# E22-XXXMXXS.net
KiCad netlist of a schematic drawn in EAGLE
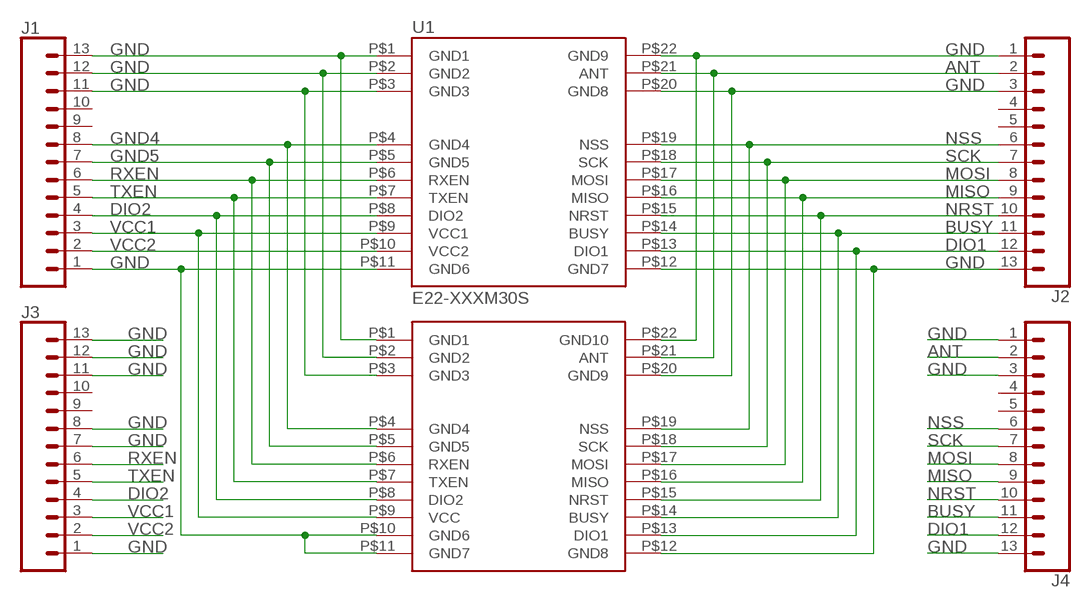
[diagram p0: schematic, sheet 1]

(export (version "E")
  (design (tool "Eeschema 10.0.6"))
  (components
    (comp (ref "J1")
      (value "CONN_13")
      (footprint "eagle-import:1X13")
      (libsource (lib "eagle-import") (part "CONN_13"))
    )
    (comp (ref "J2")
      (value "CONN_13")
      (footprint "eagle-import:1X13")
      (libsource (lib "eagle-import") (part "CONN_13"))
    )
    (comp (ref "J3")
      (value "CONN_13")
      (footprint "eagle-import:1X13")
      (libsource (lib "eagle-import") (part "CONN_13"))
    )
    (comp (ref "J4")
      (value "CONN_13")
      (footprint "eagle-import:1X13")
      (libsource (lib "eagle-import") (part "CONN_13"))
    )
    (comp (ref "U$1")
      (value "E22-XXXM22S")
      (footprint "eagle-import:E22-XXXM22S")
      (libsource (lib "eagle-import") (part "E22-XXXM22S"))
    )
    (comp (ref "U1")
      (value "E22-XXXM30S")
      (footprint "eagle-import:E22-XXXM30S")
      (libsource (lib "eagle-import") (part "E22-XXXM30S"))
    )
  )
  (nets
    (net (code "1") (name "/ANT") (class "Default")
      (node (ref "J2") (pin "2") (pinfunction "2_2") (pintype "passive"))
      (node (ref "J4") (pin "2") (pinfunction "2_2") (pintype "passive"))
      (node (ref "U$1") (pin "P$21") (pinfunction "ANT_P$21") (pintype "bidirectional"))
      (node (ref "U1") (pin "P$21") (pinfunction "ANT_P$21") (pintype "bidirectional"))
    )
    (net (code "2") (name "/BUSY") (class "Default")
      (node (ref "J2") (pin "11") (pinfunction "11_11") (pintype "passive"))
      (node (ref "J4") (pin "11") (pinfunction "11_11") (pintype "passive"))
      (node (ref "U$1") (pin "P$14") (pinfunction "BUSY_P$14") (pintype "bidirectional"))
      (node (ref "U1") (pin "P$14") (pinfunction "BUSY_P$14") (pintype "bidirectional"))
    )
    (net (code "3") (name "/DIO1") (class "Default")
      (node (ref "J2") (pin "12") (pinfunction "12_12") (pintype "passive"))
      (node (ref "J4") (pin "12") (pinfunction "12_12") (pintype "passive"))
      (node (ref "U$1") (pin "P$13") (pinfunction "DIO1_P$13") (pintype "bidirectional"))
      (node (ref "U1") (pin "P$13") (pinfunction "DIO1_P$13") (pintype "bidirectional"))
    )
    (net (code "4") (name "/DIO2") (class "Default")
      (node (ref "J1") (pin "4") (pinfunction "4_4") (pintype "passive"))
      (node (ref "J3") (pin "4") (pinfunction "4_4") (pintype "passive"))
      (node (ref "U$1") (pin "P$8") (pinfunction "DIO2_P$8") (pintype "bidirectional"))
      (node (ref "U1") (pin "P$8") (pinfunction "DIO2_P$8") (pintype "bidirectional"))
    )
    (net (code "5") (name "/GND") (class "Default")
      (node (ref "J1") (pin "1") (pinfunction "1_1") (pintype "passive"))
      (node (ref "J1") (pin "11") (pinfunction "11_11") (pintype "passive"))
      (node (ref "J1") (pin "12") (pinfunction "12_12") (pintype "passive"))
      (node (ref "J1") (pin "13") (pinfunction "13_13") (pintype "passive"))
      (node (ref "J2") (pin "1") (pinfunction "1_1") (pintype "passive"))
      (node (ref "J2") (pin "13") (pinfunction "13_13") (pintype "passive"))
      (node (ref "J2") (pin "3") (pinfunction "3_3") (pintype "passive"))
      (node (ref "J3") (pin "1") (pinfunction "1_1") (pintype "passive"))
      (node (ref "J3") (pin "11") (pinfunction "11_11") (pintype "passive"))
      (node (ref "J3") (pin "12") (pinfunction "12_12") (pintype "passive"))
      (node (ref "J3") (pin "13") (pinfunction "13_13") (pintype "passive"))
      (node (ref "J3") (pin "7") (pinfunction "7_7") (pintype "passive"))
      (node (ref "J3") (pin "8") (pinfunction "8_8") (pintype "passive"))
      (node (ref "J4") (pin "1") (pinfunction "1_1") (pintype "passive"))
      (node (ref "J4") (pin "13") (pinfunction "13_13") (pintype "passive"))
      (node (ref "J4") (pin "3") (pinfunction "3_3") (pintype "passive"))
      (node (ref "U$1") (pin "P$1") (pinfunction "GND1_P$1") (pintype "bidirectional"))
      (node (ref "U$1") (pin "P$10") (pinfunction "GND6_P$10") (pintype "bidirectional"))
      (node (ref "U$1") (pin "P$11") (pinfunction "GND7_P$11") (pintype "bidirectional"))
      (node (ref "U$1") (pin "P$12") (pinfunction "GND8_P$12") (pintype "bidirectional"))
      (node (ref "U$1") (pin "P$2") (pinfunction "GND2_P$2") (pintype "bidirectional"))
      (node (ref "U$1") (pin "P$20") (pinfunction "GND9_P$20") (pintype "bidirectional"))
      (node (ref "U$1") (pin "P$22") (pinfunction "GND10_P$22") (pintype "bidirectional"))
      (node (ref "U$1") (pin "P$3") (pinfunction "GND3_P$3") (pintype "bidirectional"))
      (node (ref "U1") (pin "P$1") (pinfunction "GND1_P$1") (pintype "bidirectional"))
      (node (ref "U1") (pin "P$11") (pinfunction "GND6_P$11") (pintype "bidirectional"))
      (node (ref "U1") (pin "P$12") (pinfunction "GND7_P$12") (pintype "bidirectional"))
      (node (ref "U1") (pin "P$2") (pinfunction "GND2_P$2") (pintype "bidirectional"))
      (node (ref "U1") (pin "P$20") (pinfunction "GND8_P$20") (pintype "bidirectional"))
      (node (ref "U1") (pin "P$22") (pinfunction "GND9_P$22") (pintype "bidirectional"))
      (node (ref "U1") (pin "P$3") (pinfunction "GND3_P$3") (pintype "bidirectional"))
    )
    (net (code "6") (name "/GND4") (class "Default")
      (node (ref "J1") (pin "8") (pinfunction "8_8") (pintype "passive"))
      (node (ref "U$1") (pin "P$4") (pinfunction "GND4_P$4") (pintype "bidirectional"))
      (node (ref "U1") (pin "P$4") (pinfunction "GND4_P$4") (pintype "bidirectional"))
    )
    (net (code "7") (name "/GND5") (class "Default")
      (node (ref "J1") (pin "7") (pinfunction "7_7") (pintype "passive"))
      (node (ref "U$1") (pin "P$5") (pinfunction "GND5_P$5") (pintype "bidirectional"))
      (node (ref "U1") (pin "P$5") (pinfunction "GND5_P$5") (pintype "bidirectional"))
    )
    (net (code "8") (name "/MISO") (class "Default")
      (node (ref "J2") (pin "9") (pinfunction "9_9") (pintype "passive"))
      (node (ref "J4") (pin "9") (pinfunction "9_9") (pintype "passive"))
      (node (ref "U$1") (pin "P$16") (pinfunction "MISO_P$16") (pintype "bidirectional"))
      (node (ref "U1") (pin "P$16") (pinfunction "MISO_P$16") (pintype "bidirectional"))
    )
    (net (code "9") (name "/MOSI") (class "Default")
      (node (ref "J2") (pin "8") (pinfunction "8_8") (pintype "passive"))
      (node (ref "J4") (pin "8") (pinfunction "8_8") (pintype "passive"))
      (node (ref "U$1") (pin "P$17") (pinfunction "MOSI_P$17") (pintype "bidirectional"))
      (node (ref "U1") (pin "P$17") (pinfunction "MOSI_P$17") (pintype "bidirectional"))
    )
    (net (code "10") (name "/NRST") (class "Default")
      (node (ref "J2") (pin "10") (pinfunction "10_10") (pintype "passive"))
      (node (ref "J4") (pin "10") (pinfunction "10_10") (pintype "passive"))
      (node (ref "U$1") (pin "P$15") (pinfunction "NRST_P$15") (pintype "bidirectional"))
      (node (ref "U1") (pin "P$15") (pinfunction "NRST_P$15") (pintype "bidirectional"))
    )
    (net (code "11") (name "/NSS") (class "Default")
      (node (ref "J2") (pin "6") (pinfunction "6_6") (pintype "passive"))
      (node (ref "J4") (pin "6") (pinfunction "6_6") (pintype "passive"))
      (node (ref "U$1") (pin "P$19") (pinfunction "NSS_P$19") (pintype "bidirectional"))
      (node (ref "U1") (pin "P$19") (pinfunction "NSS_P$19") (pintype "bidirectional"))
    )
    (net (code "12") (name "/RXEN") (class "Default")
      (node (ref "J1") (pin "6") (pinfunction "6_6") (pintype "passive"))
      (node (ref "J3") (pin "6") (pinfunction "6_6") (pintype "passive"))
      (node (ref "U$1") (pin "P$6") (pinfunction "RXEN_P$6") (pintype "bidirectional"))
      (node (ref "U1") (pin "P$6") (pinfunction "RXEN_P$6") (pintype "bidirectional"))
    )
    (net (code "13") (name "/SCK") (class "Default")
      (node (ref "J2") (pin "7") (pinfunction "7_7") (pintype "passive"))
      (node (ref "J4") (pin "7") (pinfunction "7_7") (pintype "passive"))
      (node (ref "U$1") (pin "P$18") (pinfunction "SCK_P$18") (pintype "bidirectional"))
      (node (ref "U1") (pin "P$18") (pinfunction "SCK_P$18") (pintype "bidirectional"))
    )
    (net (code "14") (name "/TXEN") (class "Default")
      (node (ref "J1") (pin "5") (pinfunction "5_5") (pintype "passive"))
      (node (ref "J3") (pin "5") (pinfunction "5_5") (pintype "passive"))
      (node (ref "U$1") (pin "P$7") (pinfunction "TXEN_P$7") (pintype "bidirectional"))
      (node (ref "U1") (pin "P$7") (pinfunction "TXEN_P$7") (pintype "bidirectional"))
    )
    (net (code "15") (name "/VCC1") (class "Default")
      (node (ref "J1") (pin "3") (pinfunction "3_3") (pintype "passive"))
      (node (ref "J3") (pin "3") (pinfunction "3_3") (pintype "passive"))
      (node (ref "U$1") (pin "P$9") (pinfunction "VCC_P$9") (pintype "bidirectional"))
      (node (ref "U1") (pin "P$9") (pinfunction "VCC1_P$9") (pintype "bidirectional"))
    )
    (net (code "16") (name "/VCC2") (class "Default")
      (node (ref "J1") (pin "2") (pinfunction "2_2") (pintype "passive"))
      (node (ref "J3") (pin "2") (pinfunction "2_2") (pintype "passive"))
      (node (ref "U1") (pin "P$10") (pinfunction "VCC2_P$10") (pintype "bidirectional"))
    )
    (net (code "17") (name "unconnected-(J1-Pad9)") (class "Default")
      (node (ref "J1") (pin "9") (pinfunction "9_9") (pintype "passive"))
    )
    (net (code "18") (name "unconnected-(J1-Pad10)") (class "Default")
      (node (ref "J1") (pin "10") (pinfunction "10_10") (pintype "passive"))
    )
    (net (code "19") (name "unconnected-(J2-Pad4)") (class "Default")
      (node (ref "J2") (pin "4") (pinfunction "4_4") (pintype "passive"))
    )
    (net (code "20") (name "unconnected-(J2-Pad5)") (class "Default")
      (node (ref "J2") (pin "5") (pinfunction "5_5") (pintype "passive"))
    )
    (net (code "21") (name "unconnected-(J3-Pad9)") (class "Default")
      (node (ref "J3") (pin "9") (pinfunction "9_9") (pintype "passive"))
    )
    (net (code "22") (name "unconnected-(J3-Pad10)") (class "Default")
      (node (ref "J3") (pin "10") (pinfunction "10_10") (pintype "passive"))
    )
    (net (code "23") (name "unconnected-(J4-Pad4)") (class "Default")
      (node (ref "J4") (pin "4") (pinfunction "4_4") (pintype "passive"))
    )
    (net (code "24") (name "unconnected-(J4-Pad5)") (class "Default")
      (node (ref "J4") (pin "5") (pinfunction "5_5") (pintype "passive"))
    )
  )
)
